# AirSensor.net
KiCad netlist of a schematic drawn in EAGLE
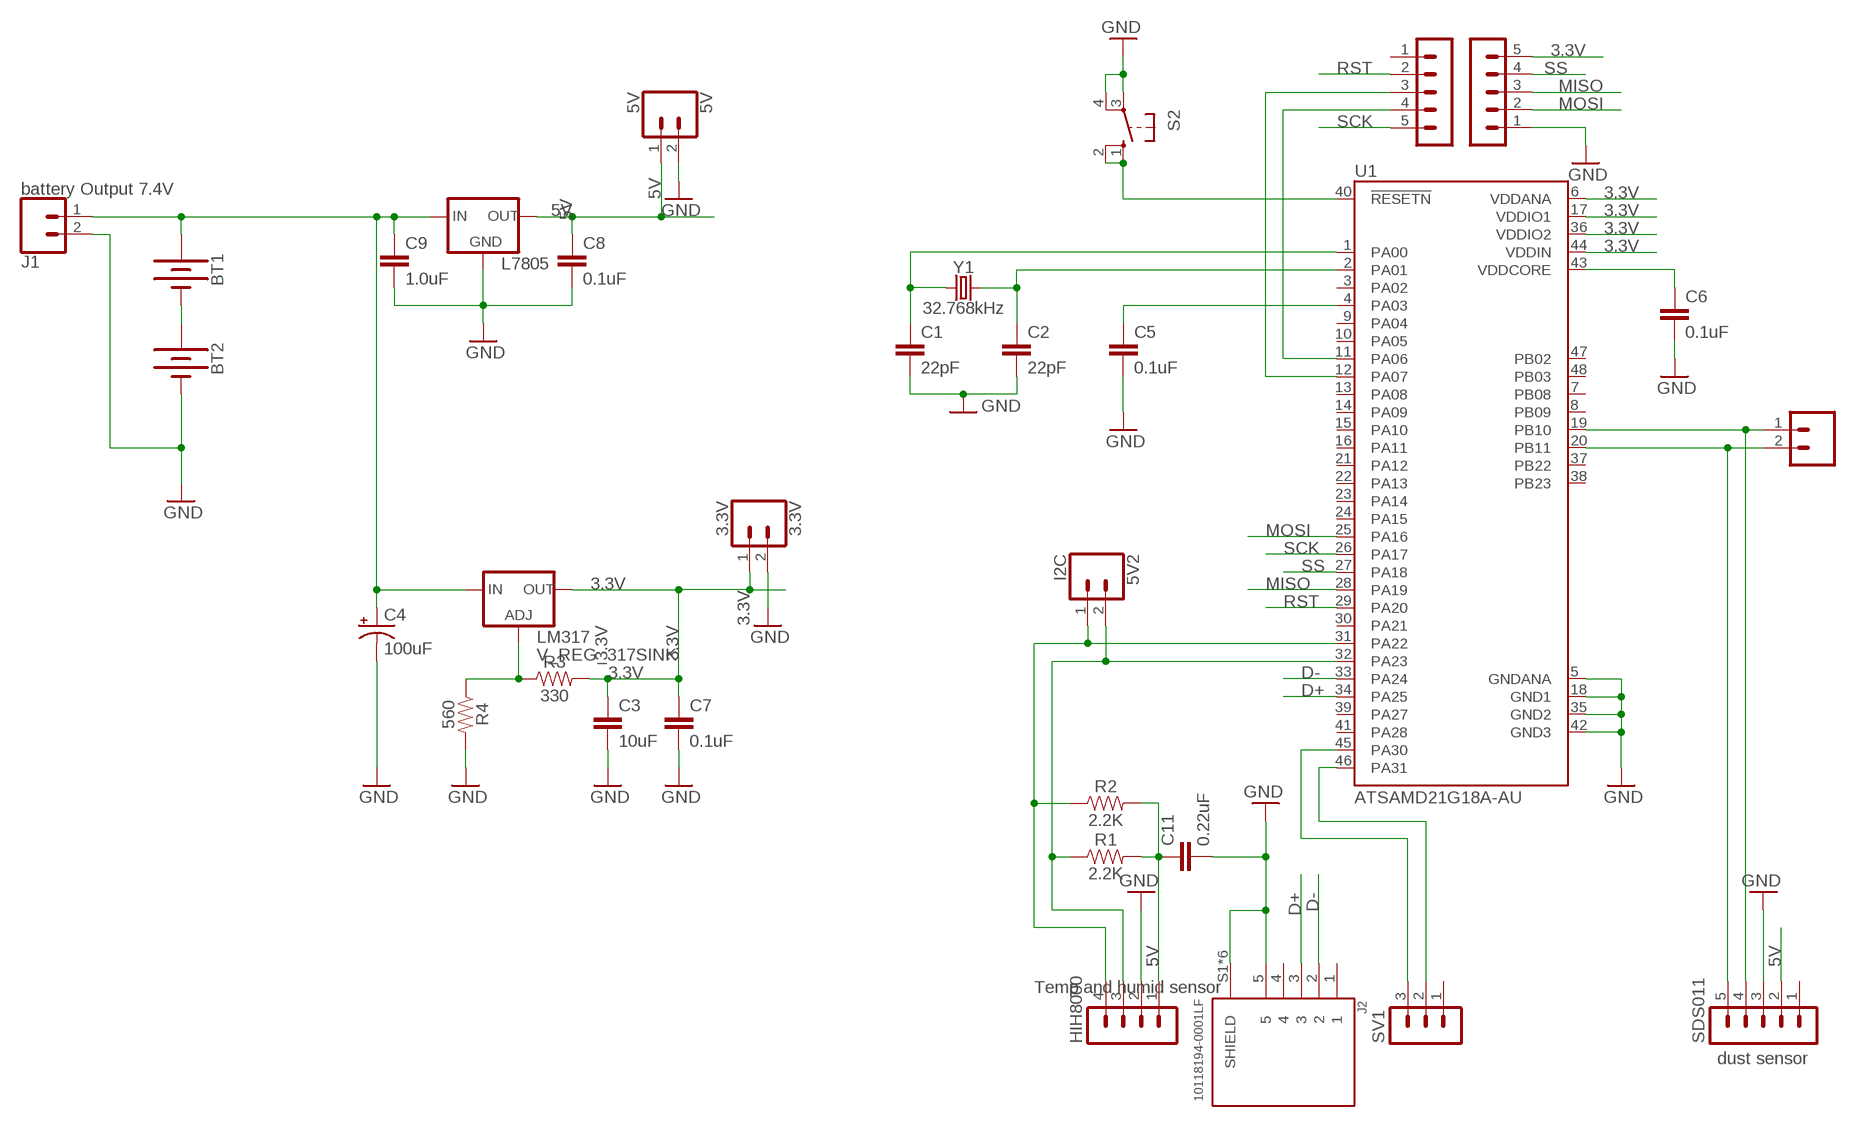
[diagram p0: schematic, sheet 1]

(export (version "E")
  (design (tool "Eeschema 10.0.6"))
  (components
    (comp (ref "3.3V")
      (value "3.3V")
      (footprint "eagle-import:1X02")
      (libsource (lib "eagle-import") (part "CONN_02"))
    )
    (comp (ref "5V")
      (value "5V")
      (footprint "eagle-import:1X02")
      (libsource (lib "eagle-import") (part "CONN_02"))
    )
    (comp (ref "5V1")
      (value "UART")
      (footprint "eagle-import:1X02")
      (libsource (lib "eagle-import") (part "CONN_02"))
    )
    (comp (ref "5V2")
      (value "I2C")
      (footprint "eagle-import:1X02")
      (libsource (lib "eagle-import") (part "CONN_02"))
    )
    (comp (ref "BT1")
      (value "BATTERY-18650")
      (footprint "eagle-import:BATTERY_18650-HOLDER")
      (libsource (lib "eagle-import") (part "BATTERY-18650"))
    )
    (comp (ref "BT2")
      (value "BATTERY-18650")
      (footprint "eagle-import:BATTERY_18650-HOLDER")
      (libsource (lib "eagle-import") (part "BATTERY-18650"))
    )
    (comp (ref "C1")
      (value "22pF")
      (footprint "eagle-import:0805")
      (libsource (lib "eagle-import") (part "1.0UF-0805-25V-10%"))
    )
    (comp (ref "C2")
      (value "22pF")
      (footprint "eagle-import:0805")
      (libsource (lib "eagle-import") (part "1.0UF-0805-25V-10%"))
    )
    (comp (ref "C3")
      (value "10uF")
      (footprint "eagle-import:0805")
      (libsource (lib "eagle-import") (part "1.0UF-0805-25V-10%"))
    )
    (comp (ref "C4")
      (value "100uF")
      (footprint "eagle-import:CPOL-RADIAL-2.5MM-6.5MM")
      (libsource (lib "eagle-import") (part "100UF-POLAR-RADIAL-2.5MM-25V-20%"))
    )
    (comp (ref "C5")
      (value "0.1uF")
      (footprint "eagle-import:0805")
      (libsource (lib "eagle-import") (part "1.0UF-0805-25V-10%"))
    )
    (comp (ref "C6")
      (value "0.1uF")
      (footprint "eagle-import:0805")
      (libsource (lib "eagle-import") (part "1.0UF-0805-25V-10%"))
    )
    (comp (ref "C7")
      (value "0.1uF")
      (footprint "eagle-import:0805")
      (libsource (lib "eagle-import") (part "1.0UF-0805-25V-10%"))
    )
    (comp (ref "C8")
      (value "0.1uF")
      (footprint "eagle-import:0805")
      (libsource (lib "eagle-import") (part "1.0UF-0805-25V-10%"))
    )
    (comp (ref "C9")
      (value "1.0uF")
      (footprint "eagle-import:0805")
      (libsource (lib "eagle-import") (part "1.0UF-0805-25V-(+80/-20%)"))
    )
    (comp (ref "C11")
      (value "0.22uF")
      (footprint "eagle-import:0805")
      (libsource (lib "eagle-import") (part "1.0UF-0805-25V-10%"))
    )
    (comp (ref "HIH8000")
      (value "Temp and humid sensor")
      (footprint "eagle-import:MA04-1")
      (libsource (lib "eagle-import") (part "MA04-1"))
    )
    (comp (ref "J1")
      (value "battery Output 7.4V")
      (footprint "eagle-import:1X02")
      (libsource (lib "eagle-import") (part "CONN_02"))
    )
    (comp (ref "J2")
      (value "10118194-0001LF")
      (footprint "eagle-import:AMPHENOL_10118194-0001LF")
      (fields (field (name "MF") "Amphenol ICC (FCI)"))
      (libsource (lib "eagle-import") (part "10118194-0001LF"))
    )
    (comp (ref "L7805")
      (value "V_REG_78XXSINK")
      (footprint "eagle-import:TO220-IGO")
      (libsource (lib "eagle-import") (part "V_REG_78XXSINK"))
    )
    (comp (ref "LM317")
      (value "V_REG_317SINK")
      (footprint "eagle-import:TO220-ADJ")
      (libsource (lib "eagle-import") (part "V_REG_317SINK"))
    )
    (comp (ref "R1")
      (value "2.2K")
      (footprint "eagle-import:0805")
      (libsource (lib "eagle-import") (part "0.3OHM-0805-1/8W-1%"))
    )
    (comp (ref "R2")
      (value "2.2K")
      (footprint "eagle-import:0805")
      (libsource (lib "eagle-import") (part "0.3OHM-0805-1/8W-1%"))
    )
    (comp (ref "R3")
      (value "330")
      (footprint "eagle-import:0805")
      (libsource (lib "eagle-import") (part "0.3OHM-0805-1/8W-1%"))
    )
    (comp (ref "R4")
      (value "560")
      (footprint "eagle-import:0805")
      (libsource (lib "eagle-import") (part "0.3OHM-0805-1/8W-1%"))
    )
    (comp (ref "RFM95W")
      (value "LoRa1")
      (footprint "eagle-import:MA05-1")
      (libsource (lib "eagle-import") (part "MA05-1"))
    )
    (comp (ref "RFM95W_2")
      (value "LoRa_2")
      (footprint "eagle-import:MA05-1")
      (libsource (lib "eagle-import") (part "MA05-1"))
    )
    (comp (ref "S2")
      (value "10-XX")
      (footprint "eagle-import:B3F-10XX")
      (fields (field (name "MPN") "B3F-1000"))
      (libsource (lib "eagle-import") (part "10-XX"))
    )
    (comp (ref "SDS011")
      (value "dust sensor")
      (footprint "eagle-import:MA05-1")
      (libsource (lib "eagle-import") (part "MA05-1"))
    )
    (comp (ref "SV1")
      (value "MA03-1")
      (footprint "eagle-import:MA03-1")
      (libsource (lib "eagle-import") (part "MA03-1"))
    )
    (comp (ref "U1")
      (value "ATSAMD21G18A-AU")
      (footprint "eagle-import:QFP50P900X900X120-48N")
      (fields (field (name "MF") "Microchip"))
      (libsource (lib "eagle-import") (part "ATSAMD21G18A-AU"))
    )
    (comp (ref "Y1")
      (value "32.768kHz")
      (footprint "eagle-import:CRYSTAL-SMD-3.2X1.5MM")
      (libsource (lib "eagle-import") (part "CRYSTAL-32.768KHZSMD-3.2X1.5"))
    )
  )
  (nets
    (net (code "1") (name "/3.3V") (class "Default")
      (node (ref "3.3V") (pin "1") (pinfunction "1_1") (pintype "passive"))
      (node (ref "C3") (pin "1") (pinfunction "1_1") (pintype "passive"))
      (node (ref "C7") (pin "1") (pinfunction "1_1") (pintype "passive"))
      (node (ref "LM317") (pin "OUT") (pinfunction "OUT_OUT") (pintype "output"))
      (node (ref "R3") (pin "2") (pinfunction "2_2") (pintype "passive"))
      (node (ref "RFM95W_2") (pin "5") (pinfunction "5_5") (pintype "passive"))
      (node (ref "U1") (pin "17") (pinfunction "VDDIO1_17") (pintype "power_in"))
      (node (ref "U1") (pin "36") (pinfunction "VDDIO2_36") (pintype "power_in"))
      (node (ref "U1") (pin "44") (pinfunction "VDDIN_44") (pintype "power_in"))
      (node (ref "U1") (pin "6") (pinfunction "VDDANA_6") (pintype "power_in"))
    )
    (net (code "2") (name "/5V") (class "Default")
      (node (ref "5V") (pin "1") (pinfunction "1_1") (pintype "passive"))
      (node (ref "C11") (pin "1") (pinfunction "1_1") (pintype "passive"))
      (node (ref "C8") (pin "1") (pinfunction "1_1") (pintype "passive"))
      (node (ref "HIH8000") (pin "1") (pinfunction "1_1") (pintype "passive"))
      (node (ref "L7805") (pin "OUT") (pinfunction "OUT_OUT") (pintype "passive"))
      (node (ref "R1") (pin "2") (pinfunction "2_2") (pintype "passive"))
      (node (ref "R2") (pin "2") (pinfunction "2_2") (pintype "passive"))
      (node (ref "SDS011") (pin "2") (pinfunction "2_2") (pintype "passive"))
    )
    (net (code "3") (name "/D+") (class "Default")
      (node (ref "J2") (pin "3") (pinfunction "3_3") (pintype "passive"))
      (node (ref "U1") (pin "34") (pinfunction "PA25_34") (pintype "bidirectional"))
    )
    (net (code "4") (name "/D-") (class "Default")
      (node (ref "J2") (pin "2") (pinfunction "2_2") (pintype "passive"))
      (node (ref "U1") (pin "33") (pinfunction "PA24_33") (pintype "bidirectional"))
    )
    (net (code "5") (name "/MISO") (class "Default")
      (node (ref "RFM95W_2") (pin "3") (pinfunction "3_3") (pintype "passive"))
      (node (ref "U1") (pin "28") (pinfunction "PA19_28") (pintype "bidirectional"))
    )
    (net (code "6") (name "/MOSI") (class "Default")
      (node (ref "RFM95W_2") (pin "2") (pinfunction "2_2") (pintype "passive"))
      (node (ref "U1") (pin "25") (pinfunction "PA16_25") (pintype "bidirectional"))
    )
    (net (code "7") (name "/RST") (class "Default")
      (node (ref "RFM95W") (pin "2") (pinfunction "2_2") (pintype "passive"))
      (node (ref "U1") (pin "29") (pinfunction "PA20_29") (pintype "bidirectional"))
    )
    (net (code "8") (name "/SCK") (class "Default")
      (node (ref "RFM95W") (pin "5") (pinfunction "5_5") (pintype "passive"))
      (node (ref "U1") (pin "26") (pinfunction "PA17_26") (pintype "bidirectional"))
    )
    (net (code "9") (name "/SS") (class "Default")
      (node (ref "RFM95W_2") (pin "4") (pinfunction "4_4") (pintype "passive"))
      (node (ref "U1") (pin "27") (pinfunction "PA18_27") (pintype "bidirectional"))
    )
    (net (code "10") (name "GND") (class "Default")
      (node (ref "3.3V") (pin "2") (pinfunction "2_2") (pintype "passive"))
      (node (ref "5V") (pin "2") (pinfunction "2_2") (pintype "passive"))
      (node (ref "BT2") (pin "GND@1") (pinfunction "-_GND@1") (pintype "power_in"))
      (node (ref "C1") (pin "2") (pinfunction "2_2") (pintype "passive"))
      (node (ref "C11") (pin "2") (pinfunction "2_2") (pintype "passive"))
      (node (ref "C2") (pin "2") (pinfunction "2_2") (pintype "passive"))
      (node (ref "C3") (pin "2") (pinfunction "2_2") (pintype "passive"))
      (node (ref "C4") (pin "2") (pinfunction "-_2") (pintype "passive"))
      (node (ref "C5") (pin "2") (pinfunction "2_2") (pintype "passive"))
      (node (ref "C6") (pin "2") (pinfunction "2_2") (pintype "passive"))
      (node (ref "C7") (pin "2") (pinfunction "2_2") (pintype "passive"))
      (node (ref "C8") (pin "2") (pinfunction "2_2") (pintype "passive"))
      (node (ref "C9") (pin "2") (pinfunction "2_2") (pintype "passive"))
      (node (ref "HIH8000") (pin "2") (pinfunction "2_2") (pintype "passive"))
      (node (ref "J1") (pin "2") (pinfunction "2_2") (pintype "passive"))
      (node (ref "J2") (pin "5") (pinfunction "5_5") (pintype "passive"))
      (node (ref "J2") (pin "S1") (pinfunction "SHIELD_S1") (pintype "passive"))
      (node (ref "J2") (pin "S2") (pinfunction "SHIELD_S2") (pintype "passive"))
      (node (ref "J2") (pin "S3") (pinfunction "SHIELD_S3") (pintype "passive"))
      (node (ref "J2") (pin "S4") (pinfunction "SHIELD_S4") (pintype "passive"))
      (node (ref "J2") (pin "S5") (pinfunction "SHIELD_S5") (pintype "passive"))
      (node (ref "J2") (pin "S6") (pinfunction "SHIELD_S6") (pintype "passive"))
      (node (ref "L7805") (pin "GND") (pinfunction "GND_GND") (pintype "input"))
      (node (ref "R4") (pin "2") (pinfunction "2_2") (pintype "passive"))
      (node (ref "RFM95W_2") (pin "1") (pinfunction "1_1") (pintype "passive"))
      (node (ref "S2") (pin "3") (pinfunction "P_3") (pintype "passive"))
      (node (ref "S2") (pin "4") (pinfunction "P1_4") (pintype "passive"))
      (node (ref "SDS011") (pin "3") (pinfunction "3_3") (pintype "passive"))
      (node (ref "U1") (pin "18") (pinfunction "GND1_18") (pintype "power_in"))
      (node (ref "U1") (pin "35") (pinfunction "GND2_35") (pintype "power_in"))
      (node (ref "U1") (pin "42") (pinfunction "GND3_42") (pintype "power_in"))
      (node (ref "U1") (pin "5") (pinfunction "GNDANA_5") (pintype "power_in"))
    )
    (net (code "11") (name "Net-(BT1-+)") (class "Default")
      (node (ref "BT1") (pin "PWR@1") (pinfunction "+_PWR@1") (pintype "power_in"))
      (node (ref "C4") (pin "1") (pinfunction "+_1") (pintype "passive"))
      (node (ref "C9") (pin "1") (pinfunction "1_1") (pintype "passive"))
      (node (ref "J1") (pin "1") (pinfunction "1_1") (pintype "passive"))
      (node (ref "L7805") (pin "IN") (pinfunction "IN_IN") (pintype "input"))
      (node (ref "LM317") (pin "IN") (pinfunction "IN_IN") (pintype "input"))
    )
    (net (code "12") (name "Net-(BT1--)") (class "Default")
      (node (ref "BT1") (pin "GND@1") (pinfunction "-_GND@1") (pintype "power_in"))
      (node (ref "BT2") (pin "PWR@1") (pinfunction "+_PWR@1") (pintype "power_in"))
    )
    (net (code "13") (name "Net-(LM317-PadADJ)") (class "Default")
      (node (ref "LM317") (pin "ADJ") (pinfunction "ADJ_ADJ") (pintype "input"))
      (node (ref "R3") (pin "1") (pinfunction "1_1") (pintype "passive"))
      (node (ref "R4") (pin "1") (pinfunction "1_1") (pintype "passive"))
    )
    (net (code "14") (name "Net-(S2-S)") (class "Default")
      (node (ref "S2") (pin "1") (pinfunction "S_1") (pintype "passive"))
      (node (ref "S2") (pin "2") (pinfunction "S1_2") (pintype "passive"))
      (node (ref "U1") (pin "40") (pinfunction "~{RESETN}_40") (pintype "input"))
    )
    (net (code "15") (name "Net-(U1-PA00)") (class "Default")
      (node (ref "C1") (pin "1") (pinfunction "1_1") (pintype "passive"))
      (node (ref "U1") (pin "1") (pinfunction "PA00_1") (pintype "bidirectional"))
      (node (ref "Y1") (pin "P$1") (pinfunction "1_P$1") (pintype "passive"))
    )
    (net (code "16") (name "Net-(U1-PA01)") (class "Default")
      (node (ref "C2") (pin "1") (pinfunction "1_1") (pintype "passive"))
      (node (ref "U1") (pin "2") (pinfunction "PA01_2") (pintype "bidirectional"))
      (node (ref "Y1") (pin "P$2") (pinfunction "2_P$2") (pintype "passive"))
    )
    (net (code "17") (name "Net-(U1-PA03)") (class "Default")
      (node (ref "C5") (pin "1") (pinfunction "1_1") (pintype "passive"))
      (node (ref "U1") (pin "4") (pinfunction "PA03_4") (pintype "bidirectional"))
    )
    (net (code "18") (name "Net-(U1-PA06)") (class "Default")
      (node (ref "RFM95W") (pin "4") (pinfunction "4_4") (pintype "passive"))
      (node (ref "U1") (pin "11") (pinfunction "PA06_11") (pintype "bidirectional"))
    )
    (net (code "19") (name "Net-(U1-PA07)") (class "Default")
      (node (ref "RFM95W") (pin "3") (pinfunction "3_3") (pintype "passive"))
      (node (ref "U1") (pin "12") (pinfunction "PA07_12") (pintype "bidirectional"))
    )
    (net (code "20") (name "Net-(U1-PA22)") (class "Default")
      (node (ref "5V2") (pin "1") (pinfunction "1_1") (pintype "passive"))
      (node (ref "HIH8000") (pin "4") (pinfunction "4_4") (pintype "passive"))
      (node (ref "R2") (pin "1") (pinfunction "1_1") (pintype "passive"))
      (node (ref "U1") (pin "31") (pinfunction "PA22_31") (pintype "bidirectional"))
    )
    (net (code "21") (name "Net-(U1-PA23)") (class "Default")
      (node (ref "5V2") (pin "2") (pinfunction "2_2") (pintype "passive"))
      (node (ref "HIH8000") (pin "3") (pinfunction "3_3") (pintype "passive"))
      (node (ref "R1") (pin "1") (pinfunction "1_1") (pintype "passive"))
      (node (ref "U1") (pin "32") (pinfunction "PA23_32") (pintype "bidirectional"))
    )
    (net (code "22") (name "Net-(U1-PA30)") (class "Default")
      (node (ref "SV1") (pin "3") (pinfunction "3_3") (pintype "passive"))
      (node (ref "U1") (pin "45") (pinfunction "PA30_45") (pintype "bidirectional"))
    )
    (net (code "23") (name "Net-(U1-PA31)") (class "Default")
      (node (ref "SV1") (pin "2") (pinfunction "2_2") (pintype "passive"))
      (node (ref "U1") (pin "46") (pinfunction "PA31_46") (pintype "bidirectional"))
    )
    (net (code "24") (name "Net-(U1-PB10)") (class "Default")
      (node (ref "5V1") (pin "1") (pinfunction "1_1") (pintype "passive"))
      (node (ref "SDS011") (pin "4") (pinfunction "4_4") (pintype "passive"))
      (node (ref "U1") (pin "19") (pinfunction "PB10_19") (pintype "bidirectional"))
    )
    (net (code "25") (name "Net-(U1-PB11)") (class "Default")
      (node (ref "5V1") (pin "2") (pinfunction "2_2") (pintype "passive"))
      (node (ref "SDS011") (pin "5") (pinfunction "5_5") (pintype "passive"))
      (node (ref "U1") (pin "20") (pinfunction "PB11_20") (pintype "bidirectional"))
    )
    (net (code "26") (name "Net-(U1-VDDCORE)") (class "Default")
      (node (ref "C6") (pin "1") (pinfunction "1_1") (pintype "passive"))
      (node (ref "U1") (pin "43") (pinfunction "VDDCORE_43") (pintype "power_in"))
    )
    (net (code "27") (name "unconnected-(J2-Pad1)") (class "Default")
      (node (ref "J2") (pin "1") (pinfunction "1_1") (pintype "passive"))
    )
    (net (code "28") (name "unconnected-(J2-Pad4)") (class "Default")
      (node (ref "J2") (pin "4") (pinfunction "4_4") (pintype "passive"))
    )
    (net (code "29") (name "unconnected-(RFM95W-Pad1)") (class "Default")
      (node (ref "RFM95W") (pin "1") (pinfunction "1_1") (pintype "passive"))
    )
    (net (code "30") (name "unconnected-(SDS011-Pad1)") (class "Default")
      (node (ref "SDS011") (pin "1") (pinfunction "1_1") (pintype "passive"))
    )
    (net (code "31") (name "unconnected-(SV1-Pad1)") (class "Default")
      (node (ref "SV1") (pin "1") (pinfunction "1_1") (pintype "passive"))
    )
    (net (code "32") (name "unconnected-(U1-PA02-Pad3)") (class "Default")
      (node (ref "U1") (pin "3") (pinfunction "PA02_3") (pintype "bidirectional"))
    )
    (net (code "33") (name "unconnected-(U1-PA04-Pad9)") (class "Default")
      (node (ref "U1") (pin "9") (pinfunction "PA04_9") (pintype "bidirectional"))
    )
    (net (code "34") (name "unconnected-(U1-PA05-Pad10)") (class "Default")
      (node (ref "U1") (pin "10") (pinfunction "PA05_10") (pintype "bidirectional"))
    )
    (net (code "35") (name "unconnected-(U1-PA08-Pad13)") (class "Default")
      (node (ref "U1") (pin "13") (pinfunction "PA08_13") (pintype "bidirectional"))
    )
    (net (code "36") (name "unconnected-(U1-PA09-Pad14)") (class "Default")
      (node (ref "U1") (pin "14") (pinfunction "PA09_14") (pintype "bidirectional"))
    )
    (net (code "37") (name "unconnected-(U1-PA10-Pad15)") (class "Default")
      (node (ref "U1") (pin "15") (pinfunction "PA10_15") (pintype "bidirectional"))
    )
    (net (code "38") (name "unconnected-(U1-PA11-Pad16)") (class "Default")
      (node (ref "U1") (pin "16") (pinfunction "PA11_16") (pintype "bidirectional"))
    )
    (net (code "39") (name "unconnected-(U1-PA12-Pad21)") (class "Default")
      (node (ref "U1") (pin "21") (pinfunction "PA12_21") (pintype "bidirectional"))
    )
    (net (code "40") (name "unconnected-(U1-PA13-Pad22)") (class "Default")
      (node (ref "U1") (pin "22") (pinfunction "PA13_22") (pintype "bidirectional"))
    )
    (net (code "41") (name "unconnected-(U1-PA14-Pad23)") (class "Default")
      (node (ref "U1") (pin "23") (pinfunction "PA14_23") (pintype "bidirectional"))
    )
    (net (code "42") (name "unconnected-(U1-PA15-Pad24)") (class "Default")
      (node (ref "U1") (pin "24") (pinfunction "PA15_24") (pintype "bidirectional"))
    )
    (net (code "43") (name "unconnected-(U1-PA21-Pad30)") (class "Default")
      (node (ref "U1") (pin "30") (pinfunction "PA21_30") (pintype "bidirectional"))
    )
    (net (code "44") (name "unconnected-(U1-PA27-Pad39)") (class "Default")
      (node (ref "U1") (pin "39") (pinfunction "PA27_39") (pintype "bidirectional"))
    )
    (net (code "45") (name "unconnected-(U1-PA28-Pad41)") (class "Default")
      (node (ref "U1") (pin "41") (pinfunction "PA28_41") (pintype "bidirectional"))
    )
    (net (code "46") (name "unconnected-(U1-PB02-Pad47)") (class "Default")
      (node (ref "U1") (pin "47") (pinfunction "PB02_47") (pintype "bidirectional"))
    )
    (net (code "47") (name "unconnected-(U1-PB03-Pad48)") (class "Default")
      (node (ref "U1") (pin "48") (pinfunction "PB03_48") (pintype "bidirectional"))
    )
    (net (code "48") (name "unconnected-(U1-PB08-Pad7)") (class "Default")
      (node (ref "U1") (pin "7") (pinfunction "PB08_7") (pintype "bidirectional"))
    )
    (net (code "49") (name "unconnected-(U1-PB09-Pad8)") (class "Default")
      (node (ref "U1") (pin "8") (pinfunction "PB09_8") (pintype "bidirectional"))
    )
    (net (code "50") (name "unconnected-(U1-PB22-Pad37)") (class "Default")
      (node (ref "U1") (pin "37") (pinfunction "PB22_37") (pintype "bidirectional"))
    )
    (net (code "51") (name "unconnected-(U1-PB23-Pad38)") (class "Default")
      (node (ref "U1") (pin "38") (pinfunction "PB23_38") (pintype "bidirectional"))
    )
  )
)
